# UartSBee_v5_0.net
KiCad netlist of a schematic drawn in EAGLE
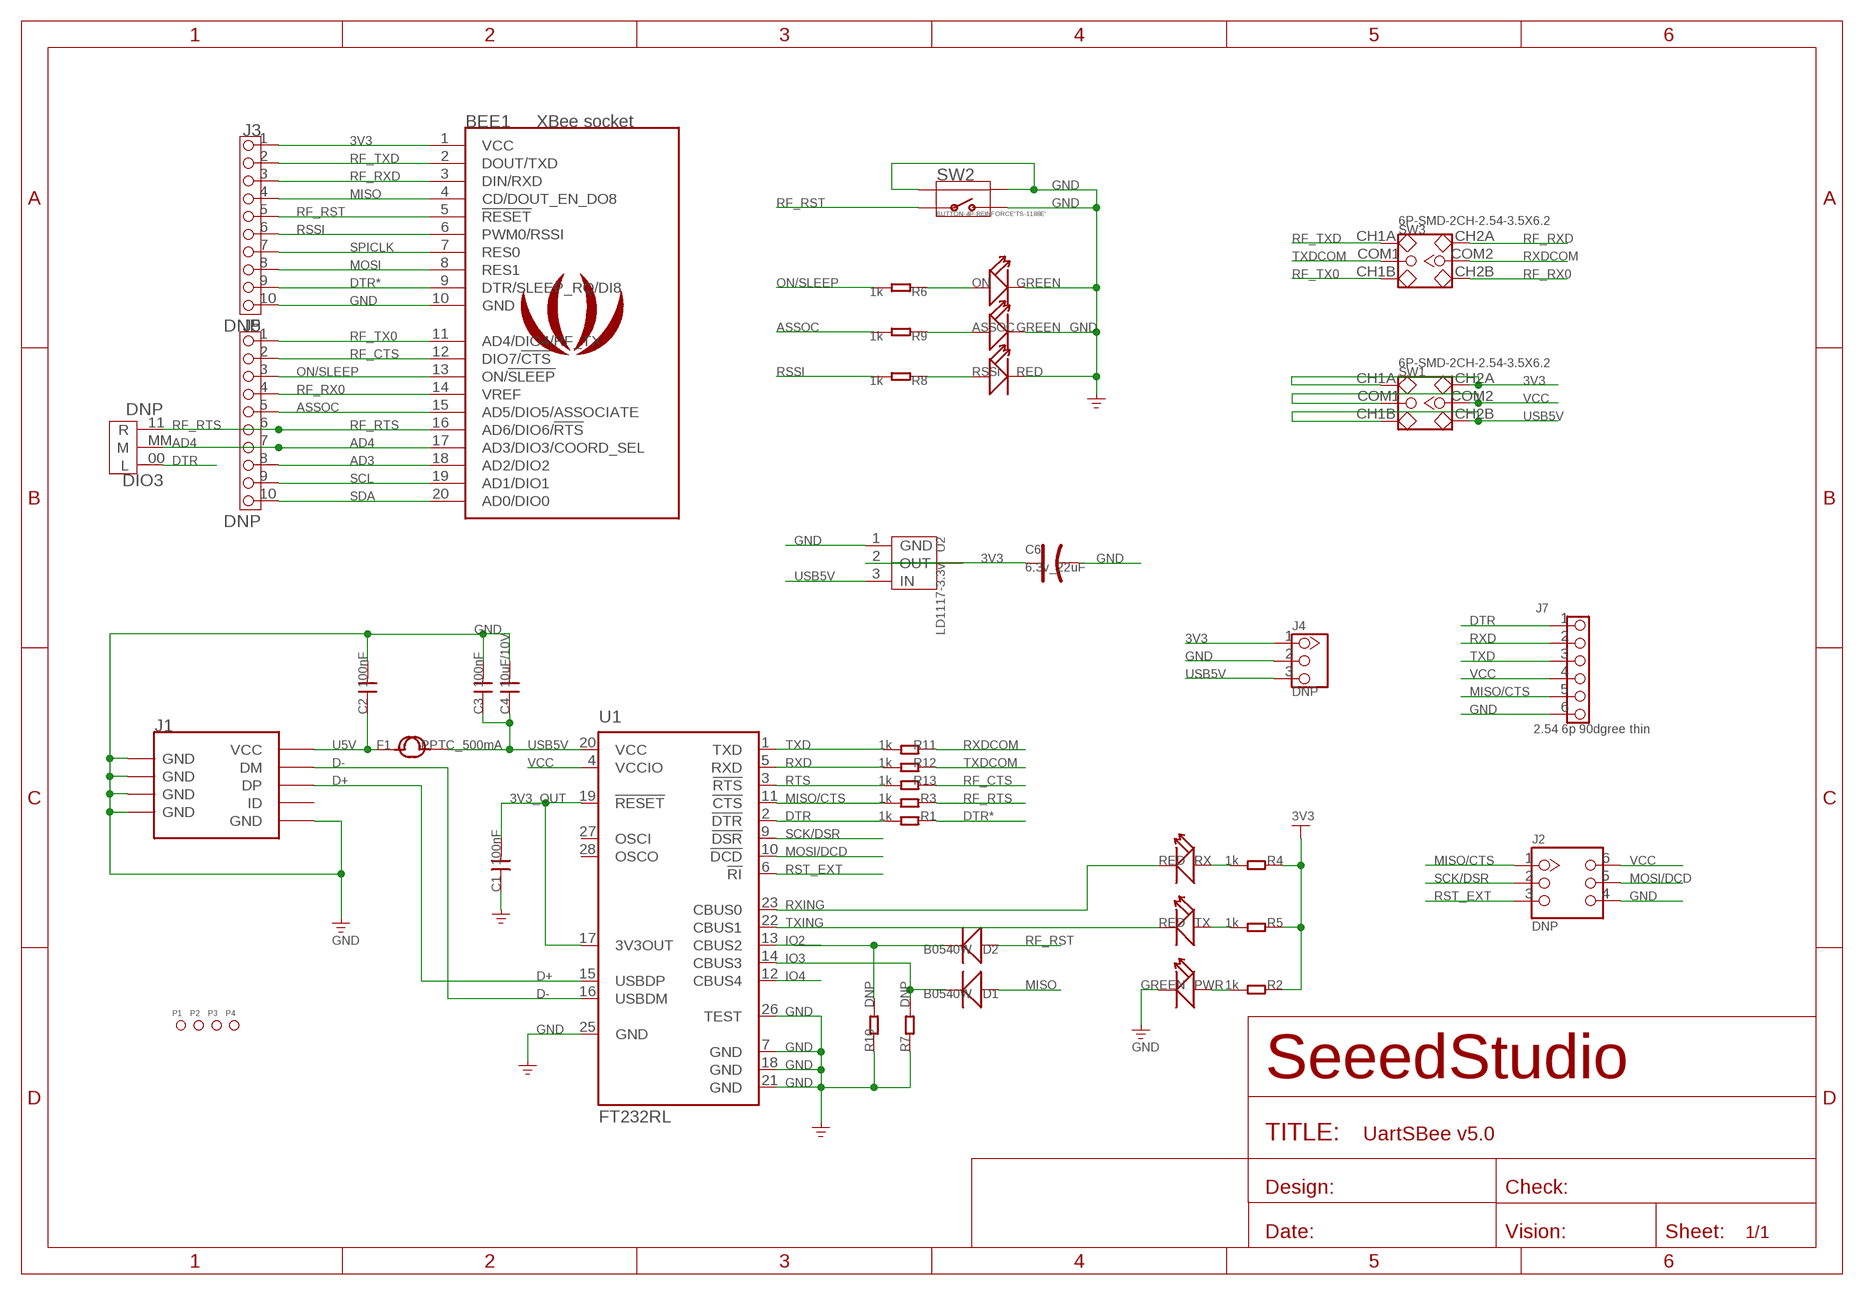
[diagram p0: schematic, sheet 1]

(export (version "E")
  (design (tool "Eeschema 10.0.6"))
  (components
    (comp (ref "ASSOC")
      (value "GREEN")
      (footprint "eagle-import:D0603")
      (libsource (lib "eagle-import") (part "LED-0603"))
    )
    (comp (ref "BEE1")
      (value "XBee socket")
      (footprint "eagle-import:BEE_BLANK")
      (libsource (lib "eagle-import") (part "BEE_BLANK"))
    )
    (comp (ref "C1")
      (value "100nF")
      (footprint "eagle-import:0603")
      (libsource (lib "eagle-import") (part "C-0603"))
    )
    (comp (ref "C2")
      (value "100nF")
      (footprint "eagle-import:0603")
      (libsource (lib "eagle-import") (part "C-0603"))
    )
    (comp (ref "C3")
      (value "100nF")
      (footprint "eagle-import:0603")
      (libsource (lib "eagle-import") (part "C-0603"))
    )
    (comp (ref "C4")
      (value "10uF/10V")
      (footprint "eagle-import:0805")
      (libsource (lib "eagle-import") (part "C-0805"))
    )
    (comp (ref "C6")
      (value "6.3v_22uF")
      (footprint "eagle-import:AVX-A")
      (libsource (lib "eagle-import") (part "CAP_AVX_A"))
    )
    (comp (ref "D1")
      (value "B0540W")
      (footprint "eagle-import:SOD123-2.7X1.6")
      (libsource (lib "eagle-import") (part "D'MBR0520LT1'"))
    )
    (comp (ref "D2")
      (value "B0540W")
      (footprint "eagle-import:SOD123-2.7X1.6")
      (libsource (lib "eagle-import") (part "D'MBR0520LT1'"))
    )
    (comp (ref "DIO3")
      (value "DNP")
      (footprint "eagle-import:3P-SMD-4.1X1.5")
      (libsource (lib "eagle-import") (part "PAD-JUMPER-3P-4040"))
    )
    (comp (ref "F1")
      (value "PPTC_500mA")
      (footprint "eagle-import:F1206")
      (libsource (lib "eagle-import") (part "FUSE'1206'"))
    )
    (comp (ref "J1")
      (value "USB-MINIUSB-5P-MICRO")
      (footprint "eagle-import:MICRO-USB")
      (libsource (lib "eagle-import") (part "USB-MINIUSB-5P-MICRO"))
    )
    (comp (ref "J2")
      (value "DNP")
      (footprint "eagle-import:CK_2X3")
      (libsource (lib "eagle-import") (part "CK_2X3_DD"))
    )
    (comp (ref "J3")
      (value "DNP")
      (footprint "eagle-import:10P-2.54-LEADED")
      (libsource (lib "eagle-import") (part "HEADER-10P-2.54"))
    )
    (comp (ref "J4")
      (value "DNP")
      (footprint "eagle-import:3P-2.54-LEADED")
      (libsource (lib "eagle-import") (part "HEADER-3P-2.54"))
    )
    (comp (ref "J5")
      (value "DNP")
      (footprint "eagle-import:10P-2.54-LEADED")
      (libsource (lib "eagle-import") (part "HEADER-10P-2.54"))
    )
    (comp (ref "J7")
      (value "2.54 6p 90dgree thin")
      (footprint "eagle-import:6P-2.54-LEADED")
      (libsource (lib "eagle-import") (part "HEADER-6P-LEADED-2.54"))
    )
    (comp (ref "LOGO1")
      (value "LOGO_COPPER150X124")
      (footprint "eagle-import:LOGO_COPPER_150X124")
      (libsource (lib "eagle-import") (part "LOGO_COPPER150X124"))
    )
    (comp (ref "ON")
      (value "GREEN")
      (footprint "eagle-import:D0603")
      (libsource (lib "eagle-import") (part "LED-0603"))
    )
    (comp (ref "P1")
      (value "PAD-MARK")
      (footprint "eagle-import:ROUND-MARK-1.0")
      (fields (field (name "PARTNO") "DNP"))
      (libsource (lib "eagle-import") (part "PAD-MARK"))
    )
    (comp (ref "P2")
      (value "PAD-MARK")
      (footprint "eagle-import:ROUND-MARK-1.0")
      (fields (field (name "PARTNO") "DNP"))
      (libsource (lib "eagle-import") (part "PAD-MARK"))
    )
    (comp (ref "P3")
      (value "PAD-MARK")
      (footprint "eagle-import:ROUND-MARK-1.0")
      (fields (field (name "PARTNO") "DNP"))
      (libsource (lib "eagle-import") (part "PAD-MARK"))
    )
    (comp (ref "P4")
      (value "PAD-MARK")
      (footprint "eagle-import:ROUND-MARK-1.0")
      (fields (field (name "PARTNO") "DNP"))
      (libsource (lib "eagle-import") (part "PAD-MARK"))
    )
    (comp (ref "PWR")
      (value "GREEN")
      (footprint "eagle-import:D0603")
      (libsource (lib "eagle-import") (part "LED-0603"))
    )
    (comp (ref "R1")
      (value "1k")
      (footprint "eagle-import:R0603")
      (libsource (lib "eagle-import") (part "R-0603"))
    )
    (comp (ref "R2")
      (value "1k")
      (footprint "eagle-import:R0603")
      (libsource (lib "eagle-import") (part "R-0603"))
    )
    (comp (ref "R3")
      (value "1k")
      (footprint "eagle-import:R0603")
      (libsource (lib "eagle-import") (part "R-0603"))
    )
    (comp (ref "R4")
      (value "1k")
      (footprint "eagle-import:R0603")
      (libsource (lib "eagle-import") (part "R-0603"))
    )
    (comp (ref "R5")
      (value "1k")
      (footprint "eagle-import:R0603")
      (libsource (lib "eagle-import") (part "R-0603"))
    )
    (comp (ref "R6")
      (value "1k")
      (footprint "eagle-import:R0603")
      (libsource (lib "eagle-import") (part "R-0603"))
    )
    (comp (ref "R7")
      (value "DNP")
      (footprint "eagle-import:R0603")
      (libsource (lib "eagle-import") (part "R-0603"))
    )
    (comp (ref "R8")
      (value "1k")
      (footprint "eagle-import:R0603")
      (libsource (lib "eagle-import") (part "R-0603"))
    )
    (comp (ref "R9")
      (value "1k")
      (footprint "eagle-import:R0603")
      (libsource (lib "eagle-import") (part "R-0603"))
    )
    (comp (ref "R10")
      (value "DNP")
      (footprint "eagle-import:R0603")
      (libsource (lib "eagle-import") (part "R-0603"))
    )
    (comp (ref "R11")
      (value "1k")
      (footprint "eagle-import:R0603")
      (libsource (lib "eagle-import") (part "R-0603"))
    )
    (comp (ref "R12")
      (value "1k")
      (footprint "eagle-import:R0603")
      (libsource (lib "eagle-import") (part "R-0603"))
    )
    (comp (ref "R13")
      (value "1k")
      (footprint "eagle-import:R0603")
      (libsource (lib "eagle-import") (part "R-0603"))
    )
    (comp (ref "RSSI")
      (value "RED")
      (footprint "eagle-import:D0603")
      (libsource (lib "eagle-import") (part "LED-0603"))
    )
    (comp (ref "RX")
      (value "RED")
      (footprint "eagle-import:D0603")
      (libsource (lib "eagle-import") (part "LED-0603"))
    )
    (comp (ref "SW1")
      (value "6P-SMD-2CH-2.54-3.5X6.2")
      (footprint "eagle-import:6P-SMD-2CH-2.54-3.5X6.2")
      (libsource (lib "eagle-import") (part "SWITCH-2CH-6P-SMD"))
    )
    (comp (ref "SW2")
      (value "BUTTON-4P-REINFORCE'TS-1188E'")
      (footprint "eagle-import:4P-SMD-7X3.5X3.5H")
      (libsource (lib "eagle-import") (part "BUTTON-4P-REINFORCE'TS-1188E'"))
    )
    (comp (ref "SW3")
      (value "6P-SMD-2CH-2.54-3.5X6.2")
      (footprint "eagle-import:6P-SMD-2CH-2.54-3.5X6.2")
      (libsource (lib "eagle-import") (part "SWITCH-2CH-6P-SMD"))
    )
    (comp (ref "TX")
      (value "RED")
      (footprint "eagle-import:D0603")
      (libsource (lib "eagle-import") (part "LED-0603"))
    )
    (comp (ref "U1")
      (value "FT232RL")
      (footprint "eagle-import:SSOP28")
      (libsource (lib "eagle-import") (part "FT232RL"))
    )
    (comp (ref "U2")
      (value "LD1117-3.3v")
      (footprint "eagle-import:SOT89")
      (libsource (lib "eagle-import") (part "LD1117SOT89"))
    )
  )
  (nets
    (net (code "1") (name "/3V3_OUT") (class "Default")
      (node (ref "C1") (pin "2") (pinfunction "2_2") (pintype "passive"))
      (node (ref "U1") (pin "17") (pinfunction "3V3OUT_17") (pintype "input"))
      (node (ref "U1") (pin "19") (pinfunction "~{RESET}_19") (pintype "input"))
    )
    (net (code "2") (name "/AD3") (class "Default")
      (node (ref "BEE1") (pin "18") (pinfunction "AD2/DIO2_18") (pintype "bidirectional"))
      (node (ref "J5") (pin "8") (pinfunction "8_8") (pintype "bidirectional"))
    )
    (net (code "3") (name "/AD4") (class "Default")
      (node (ref "BEE1") (pin "17") (pinfunction "AD3/DIO3/COORD_SEL_17") (pintype "bidirectional"))
      (node (ref "DIO3") (pin "MM") (pinfunction "M_MM") (pintype "bidirectional"))
      (node (ref "J5") (pin "7") (pinfunction "7_7") (pintype "bidirectional"))
    )
    (net (code "4") (name "/ASSOC") (class "Default")
      (node (ref "BEE1") (pin "15") (pinfunction "AD5/DIO5/ASSOCIATE_15") (pintype "bidirectional"))
      (node (ref "J5") (pin "5") (pinfunction "5_5") (pintype "bidirectional"))
      (node (ref "R9") (pin "2") (pinfunction "2_2") (pintype "passive"))
    )
    (net (code "5") (name "/D+") (class "Default")
      (node (ref "J1") (pin "3") (pinfunction "DP_3") (pintype "bidirectional"))
      (node (ref "U1") (pin "15") (pinfunction "USBDP_15") (pintype "input"))
    )
    (net (code "6") (name "/D-") (class "Default")
      (node (ref "J1") (pin "2") (pinfunction "DM_2") (pintype "bidirectional"))
      (node (ref "U1") (pin "16") (pinfunction "USBDM_16") (pintype "input"))
    )
    (net (code "7") (name "/DTR") (class "Default")
      (node (ref "DIO3") (pin "00") (pinfunction "L_00") (pintype "bidirectional"))
      (node (ref "J7") (pin "1") (pinfunction "1_1") (pintype "bidirectional"))
      (node (ref "R1") (pin "2") (pinfunction "2_2") (pintype "passive"))
      (node (ref "U1") (pin "2") (pinfunction "~{DTR}_2") (pintype "input"))
    )
    (net (code "8") (name "/DTR*") (class "Default")
      (node (ref "BEE1") (pin "9") (pinfunction "DTR/SLEEP_RQ/DI8_9") (pintype "bidirectional"))
      (node (ref "J3") (pin "9") (pinfunction "9_9") (pintype "bidirectional"))
      (node (ref "R1") (pin "1") (pinfunction "1_1") (pintype "passive"))
    )
    (net (code "9") (name "/IO2") (class "Default")
      (node (ref "D2") (pin "2") (pinfunction "-_2") (pintype "passive"))
      (node (ref "R10") (pin "2") (pinfunction "2_2") (pintype "passive"))
      (node (ref "U1") (pin "13") (pinfunction "CBUS2_13") (pintype "input"))
    )
    (net (code "10") (name "/IO3") (class "Default")
      (node (ref "D1") (pin "2") (pinfunction "-_2") (pintype "passive"))
      (node (ref "R7") (pin "2") (pinfunction "2_2") (pintype "passive"))
      (node (ref "U1") (pin "14") (pinfunction "CBUS3_14") (pintype "input"))
    )
    (net (code "11") (name "/IO4") (class "Default")
      (node (ref "U1") (pin "12") (pinfunction "CBUS4_12") (pintype "input"))
    )
    (net (code "12") (name "/MISO") (class "Default")
      (node (ref "BEE1") (pin "4") (pinfunction "CD/DOUT_EN_DO8_4") (pintype "bidirectional"))
      (node (ref "D1") (pin "1") (pinfunction "+_1") (pintype "passive"))
      (node (ref "J3") (pin "4") (pinfunction "4_4") (pintype "bidirectional"))
    )
    (net (code "13") (name "/MISO{slash}CTS") (class "Default")
      (node (ref "J2") (pin "1") (pinfunction "1_1") (pintype "bidirectional"))
      (node (ref "J7") (pin "5") (pinfunction "5_5") (pintype "bidirectional"))
      (node (ref "R3") (pin "2") (pinfunction "2_2") (pintype "passive"))
      (node (ref "U1") (pin "11") (pinfunction "~{CTS}_11") (pintype "input"))
    )
    (net (code "14") (name "/MOSI") (class "Default")
      (node (ref "BEE1") (pin "8") (pinfunction "RES1_8") (pintype "bidirectional"))
      (node (ref "J3") (pin "8") (pinfunction "8_8") (pintype "bidirectional"))
    )
    (net (code "15") (name "/MOSI{slash}DCD") (class "Default")
      (node (ref "J2") (pin "5") (pinfunction "5_5") (pintype "bidirectional"))
      (node (ref "U1") (pin "10") (pinfunction "~{DCD}_10") (pintype "input"))
    )
    (net (code "16") (name "/ON{slash}SLEEP") (class "Default")
      (node (ref "BEE1") (pin "13") (pinfunction "ON/~{SLEEP}_13") (pintype "bidirectional"))
      (node (ref "J5") (pin "3") (pinfunction "3_3") (pintype "bidirectional"))
      (node (ref "R6") (pin "2") (pinfunction "2_2") (pintype "passive"))
    )
    (net (code "17") (name "/RF_CTS") (class "Default")
      (node (ref "BEE1") (pin "12") (pinfunction "DIO7/~{CTS}_12") (pintype "bidirectional"))
      (node (ref "J5") (pin "2") (pinfunction "2_2") (pintype "bidirectional"))
      (node (ref "R13") (pin "1") (pinfunction "1_1") (pintype "passive"))
    )
    (net (code "18") (name "/RF_RST") (class "Default")
      (node (ref "BEE1") (pin "5") (pinfunction "~{RESET}_5") (pintype "bidirectional"))
      (node (ref "D2") (pin "1") (pinfunction "+_1") (pintype "passive"))
      (node (ref "J3") (pin "5") (pinfunction "5_5") (pintype "bidirectional"))
      (node (ref "SW2") (pin "1") (pinfunction "1_1") (pintype "bidirectional"))
    )
    (net (code "19") (name "/RF_RTS") (class "Default")
      (node (ref "BEE1") (pin "16") (pinfunction "AD6/DIO6/~{RTS}_16") (pintype "bidirectional"))
      (node (ref "DIO3") (pin "11") (pinfunction "R_11") (pintype "bidirectional"))
      (node (ref "J5") (pin "6") (pinfunction "6_6") (pintype "bidirectional"))
      (node (ref "R3") (pin "1") (pinfunction "1_1") (pintype "passive"))
    )
    (net (code "20") (name "/RF_RX0") (class "Default")
      (node (ref "BEE1") (pin "14") (pinfunction "VREF_14") (pintype "bidirectional"))
      (node (ref "J5") (pin "4") (pinfunction "4_4") (pintype "bidirectional"))
      (node (ref "SW3") (pin "CH2B") (pinfunction "CH2B_CH2B") (pintype "bidirectional"))
    )
    (net (code "21") (name "/RF_RXD") (class "Default")
      (node (ref "BEE1") (pin "3") (pinfunction "DIN/RXD_3") (pintype "bidirectional"))
      (node (ref "J3") (pin "3") (pinfunction "3_3") (pintype "bidirectional"))
      (node (ref "SW3") (pin "CH2A") (pinfunction "CH2A_CH2A") (pintype "bidirectional"))
    )
    (net (code "22") (name "/RF_TX0") (class "Default")
      (node (ref "BEE1") (pin "11") (pinfunction "AD4/DIO4/RF_TX_11") (pintype "bidirectional"))
      (node (ref "J5") (pin "1") (pinfunction "1_1") (pintype "bidirectional"))
      (node (ref "SW3") (pin "CH1B") (pinfunction "CH1B_CH1B") (pintype "bidirectional"))
    )
    (net (code "23") (name "/RF_TXD") (class "Default")
      (node (ref "BEE1") (pin "2") (pinfunction "DOUT/TXD_2") (pintype "bidirectional"))
      (node (ref "J3") (pin "2") (pinfunction "2_2") (pintype "bidirectional"))
      (node (ref "SW3") (pin "CH1A") (pinfunction "CH1A_CH1A") (pintype "bidirectional"))
    )
    (net (code "24") (name "/RSSI") (class "Default")
      (node (ref "BEE1") (pin "6") (pinfunction "PWM0/RSSI_6") (pintype "bidirectional"))
      (node (ref "J3") (pin "6") (pinfunction "6_6") (pintype "bidirectional"))
      (node (ref "R8") (pin "2") (pinfunction "2_2") (pintype "passive"))
    )
    (net (code "25") (name "/RST_EXT") (class "Default")
      (node (ref "J2") (pin "3") (pinfunction "3_3") (pintype "bidirectional"))
      (node (ref "U1") (pin "6") (pinfunction "~{RI}_6") (pintype "input"))
    )
    (net (code "26") (name "/RTS") (class "Default")
      (node (ref "R13") (pin "2") (pinfunction "2_2") (pintype "passive"))
      (node (ref "U1") (pin "3") (pinfunction "~{RTS}_3") (pintype "input"))
    )
    (net (code "27") (name "/RXD") (class "Default")
      (node (ref "J7") (pin "2") (pinfunction "2_2") (pintype "bidirectional"))
      (node (ref "R12") (pin "2") (pinfunction "2_2") (pintype "passive"))
      (node (ref "U1") (pin "5") (pinfunction "RXD_5") (pintype "input"))
    )
    (net (code "28") (name "/RXDCOM") (class "Default")
      (node (ref "R11") (pin "1") (pinfunction "1_1") (pintype "passive"))
      (node (ref "SW3") (pin "COM2") (pinfunction "COM2_COM2") (pintype "bidirectional"))
    )
    (net (code "29") (name "/RXING") (class "Default")
      (node (ref "RX") (pin "-") (pinfunction "-_-") (pintype "passive"))
      (node (ref "U1") (pin "23") (pinfunction "CBUS0_23") (pintype "input"))
    )
    (net (code "30") (name "/SCK{slash}DSR") (class "Default")
      (node (ref "J2") (pin "2") (pinfunction "2_2") (pintype "bidirectional"))
      (node (ref "U1") (pin "9") (pinfunction "~{DSR}_9") (pintype "input"))
    )
    (net (code "31") (name "/SCL") (class "Default")
      (node (ref "BEE1") (pin "19") (pinfunction "AD1/DIO1_19") (pintype "bidirectional"))
      (node (ref "J5") (pin "9") (pinfunction "9_9") (pintype "bidirectional"))
    )
    (net (code "32") (name "/SDA") (class "Default")
      (node (ref "BEE1") (pin "20") (pinfunction "AD0/DIO0_20") (pintype "bidirectional"))
      (node (ref "J5") (pin "10") (pinfunction "10_10") (pintype "bidirectional"))
    )
    (net (code "33") (name "/SPICLK") (class "Default")
      (node (ref "BEE1") (pin "7") (pinfunction "RES0_7") (pintype "bidirectional"))
      (node (ref "J3") (pin "7") (pinfunction "7_7") (pintype "bidirectional"))
    )
    (net (code "34") (name "/TXD") (class "Default")
      (node (ref "J7") (pin "3") (pinfunction "3_3") (pintype "bidirectional"))
      (node (ref "R11") (pin "2") (pinfunction "2_2") (pintype "passive"))
      (node (ref "U1") (pin "1") (pinfunction "TXD_1") (pintype "input"))
    )
    (net (code "35") (name "/TXDCOM") (class "Default")
      (node (ref "R12") (pin "1") (pinfunction "1_1") (pintype "passive"))
      (node (ref "SW3") (pin "COM1") (pinfunction "COM1_COM1") (pintype "bidirectional"))
    )
    (net (code "36") (name "/TXING") (class "Default")
      (node (ref "TX") (pin "-") (pinfunction "-_-") (pintype "passive"))
      (node (ref "U1") (pin "22") (pinfunction "CBUS1_22") (pintype "input"))
    )
    (net (code "37") (name "/U5V") (class "Default")
      (node (ref "C2") (pin "1") (pinfunction "1_1") (pintype "passive"))
      (node (ref "F1") (pin "1") (pinfunction "1_1") (pintype "bidirectional"))
      (node (ref "J1") (pin "1") (pinfunction "VCC_1") (pintype "bidirectional"))
    )
    (net (code "38") (name "/USB5V") (class "Default")
      (node (ref "C3") (pin "1") (pinfunction "1_1") (pintype "passive"))
      (node (ref "C4") (pin "1") (pinfunction "1_1") (pintype "passive"))
      (node (ref "F1") (pin "2") (pinfunction "2_2") (pintype "bidirectional"))
      (node (ref "J4") (pin "3") (pinfunction "P$3_3") (pintype "bidirectional"))
      (node (ref "SW1") (pin "CH1B") (pinfunction "CH1B_CH1B") (pintype "bidirectional"))
      (node (ref "SW1") (pin "CH2B") (pinfunction "CH2B_CH2B") (pintype "bidirectional"))
      (node (ref "U1") (pin "20") (pinfunction "VCC_20") (pintype "input"))
      (node (ref "U2") (pin "3") (pinfunction "IN_3") (pintype "bidirectional"))
    )
    (net (code "39") (name "/VCC") (class "Default")
      (node (ref "J2") (pin "6") (pinfunction "6_6") (pintype "bidirectional"))
      (node (ref "J7") (pin "4") (pinfunction "4_4") (pintype "bidirectional"))
      (node (ref "SW1") (pin "COM1") (pinfunction "COM1_COM1") (pintype "bidirectional"))
      (node (ref "SW1") (pin "COM2") (pinfunction "COM2_COM2") (pintype "bidirectional"))
      (node (ref "U1") (pin "4") (pinfunction "VCCIO_4") (pintype "input"))
    )
    (net (code "40") (name "GND_POWER") (class "Default")
      (node (ref "ASSOC") (pin "-") (pinfunction "-_-") (pintype "passive"))
      (node (ref "BEE1") (pin "10") (pinfunction "GND_10") (pintype "bidirectional"))
      (node (ref "C1") (pin "1") (pinfunction "1_1") (pintype "passive"))
      (node (ref "C2") (pin "2") (pinfunction "2_2") (pintype "passive"))
      (node (ref "C3") (pin "2") (pinfunction "2_2") (pintype "passive"))
      (node (ref "C4") (pin "2") (pinfunction "2_2") (pintype "passive"))
      (node (ref "C6") (pin "-") (pinfunction "-_-") (pintype "passive"))
      (node (ref "J1") (pin "5") (pinfunction "GND_5") (pintype "bidirectional"))
      (node (ref "J1") (pin "S1") (pinfunction "GND_S1") (pintype "bidirectional"))
      (node (ref "J1") (pin "S2") (pinfunction "GND_S2") (pintype "bidirectional"))
      (node (ref "J1") (pin "S3") (pinfunction "GND_S3") (pintype "bidirectional"))
      (node (ref "J1") (pin "S4") (pinfunction "GND_S4") (pintype "bidirectional"))
      (node (ref "J1") (pin "S5") (pinfunction "GND_S5") (pintype "bidirectional"))
      (node (ref "J1") (pin "S6") (pinfunction "GND_S6") (pintype "bidirectional"))
      (node (ref "J2") (pin "4") (pinfunction "4_4") (pintype "bidirectional"))
      (node (ref "J3") (pin "10") (pinfunction "10_10") (pintype "bidirectional"))
      (node (ref "J4") (pin "2") (pinfunction "P$2_2") (pintype "bidirectional"))
      (node (ref "J7") (pin "6") (pinfunction "6_6") (pintype "bidirectional"))
      (node (ref "ON") (pin "-") (pinfunction "-_-") (pintype "passive"))
      (node (ref "PWR") (pin "-") (pinfunction "-_-") (pintype "passive"))
      (node (ref "R10") (pin "1") (pinfunction "1_1") (pintype "passive"))
      (node (ref "R7") (pin "1") (pinfunction "1_1") (pintype "passive"))
      (node (ref "RSSI") (pin "-") (pinfunction "-_-") (pintype "passive"))
      (node (ref "SW2") (pin "2") (pinfunction "2_2") (pintype "bidirectional"))
      (node (ref "SW2") (pin "S1") (pinfunction "S1_S1") (pintype "bidirectional"))
      (node (ref "SW2") (pin "S2") (pinfunction "S2_S2") (pintype "bidirectional"))
      (node (ref "U1") (pin "18") (pinfunction "GND_18") (pintype "input"))
      (node (ref "U1") (pin "21") (pinfunction "GND_21") (pintype "input"))
      (node (ref "U1") (pin "25") (pinfunction "GND_25") (pintype "input"))
      (node (ref "U1") (pin "26") (pinfunction "TEST_26") (pintype "input"))
      (node (ref "U1") (pin "7") (pinfunction "GND_7") (pintype "input"))
      (node (ref "U2") (pin "1") (pinfunction "GND_1") (pintype "bidirectional"))
    )
    (net (code "41") (name "Net-(ASSOC-Pad+)") (class "Default")
      (node (ref "ASSOC") (pin "+") (pinfunction "+_+") (pintype "passive"))
      (node (ref "R9") (pin "1") (pinfunction "1_1") (pintype "passive"))
    )
    (net (code "42") (name "Net-(ON-Pad+)") (class "Default")
      (node (ref "ON") (pin "+") (pinfunction "+_+") (pintype "passive"))
      (node (ref "R6") (pin "1") (pinfunction "1_1") (pintype "passive"))
    )
    (net (code "43") (name "Net-(PWR-Pad+)") (class "Default")
      (node (ref "PWR") (pin "+") (pinfunction "+_+") (pintype "passive"))
      (node (ref "R2") (pin "2") (pinfunction "2_2") (pintype "passive"))
    )
    (net (code "44") (name "Net-(R4-Pad2)") (class "Default")
      (node (ref "R4") (pin "2") (pinfunction "2_2") (pintype "passive"))
      (node (ref "RX") (pin "+") (pinfunction "+_+") (pintype "passive"))
    )
    (net (code "45") (name "Net-(R5-Pad2)") (class "Default")
      (node (ref "R5") (pin "2") (pinfunction "2_2") (pintype "passive"))
      (node (ref "TX") (pin "+") (pinfunction "+_+") (pintype "passive"))
    )
    (net (code "46") (name "Net-(R8-Pad1)") (class "Default")
      (node (ref "R8") (pin "1") (pinfunction "1_1") (pintype "passive"))
      (node (ref "RSSI") (pin "+") (pinfunction "+_+") (pintype "passive"))
    )
    (net (code "47") (name "POWER_BAR") (class "Default")
      (node (ref "BEE1") (pin "1") (pinfunction "VCC_1") (pintype "bidirectional"))
      (node (ref "C6") (pin "+") (pinfunction "+_+") (pintype "passive"))
      (node (ref "J3") (pin "1") (pinfunction "1_1") (pintype "bidirectional"))
      (node (ref "J4") (pin "1") (pinfunction "P$1_1") (pintype "bidirectional"))
      (node (ref "R2") (pin "1") (pinfunction "1_1") (pintype "passive"))
      (node (ref "R4") (pin "1") (pinfunction "1_1") (pintype "passive"))
      (node (ref "R5") (pin "1") (pinfunction "1_1") (pintype "passive"))
      (node (ref "SW1") (pin "CH1A") (pinfunction "CH1A_CH1A") (pintype "bidirectional"))
      (node (ref "SW1") (pin "CH2A") (pinfunction "CH2A_CH2A") (pintype "bidirectional"))
      (node (ref "U2") (pin "2") (pinfunction "OUT_2") (pintype "bidirectional"))
      (node (ref "U2") (pin "4") (pinfunction "TAB_4") (pintype "bidirectional"))
    )
    (net (code "48") (name "unconnected-(J1-ID-Pad4)") (class "Default")
      (node (ref "J1") (pin "4") (pinfunction "ID_4") (pintype "bidirectional"))
    )
    (net (code "49") (name "unconnected-(U1-OSCI-Pad27)") (class "Default")
      (node (ref "U1") (pin "27") (pinfunction "OSCI_27") (pintype "input"))
    )
    (net (code "50") (name "unconnected-(U1-OSCO-Pad28)") (class "Default")
      (node (ref "U1") (pin "28") (pinfunction "OSCO_28") (pintype "input"))
    )
  )
)
